# dev_A.net
KiCad netlist of a schematic drawn in EAGLE
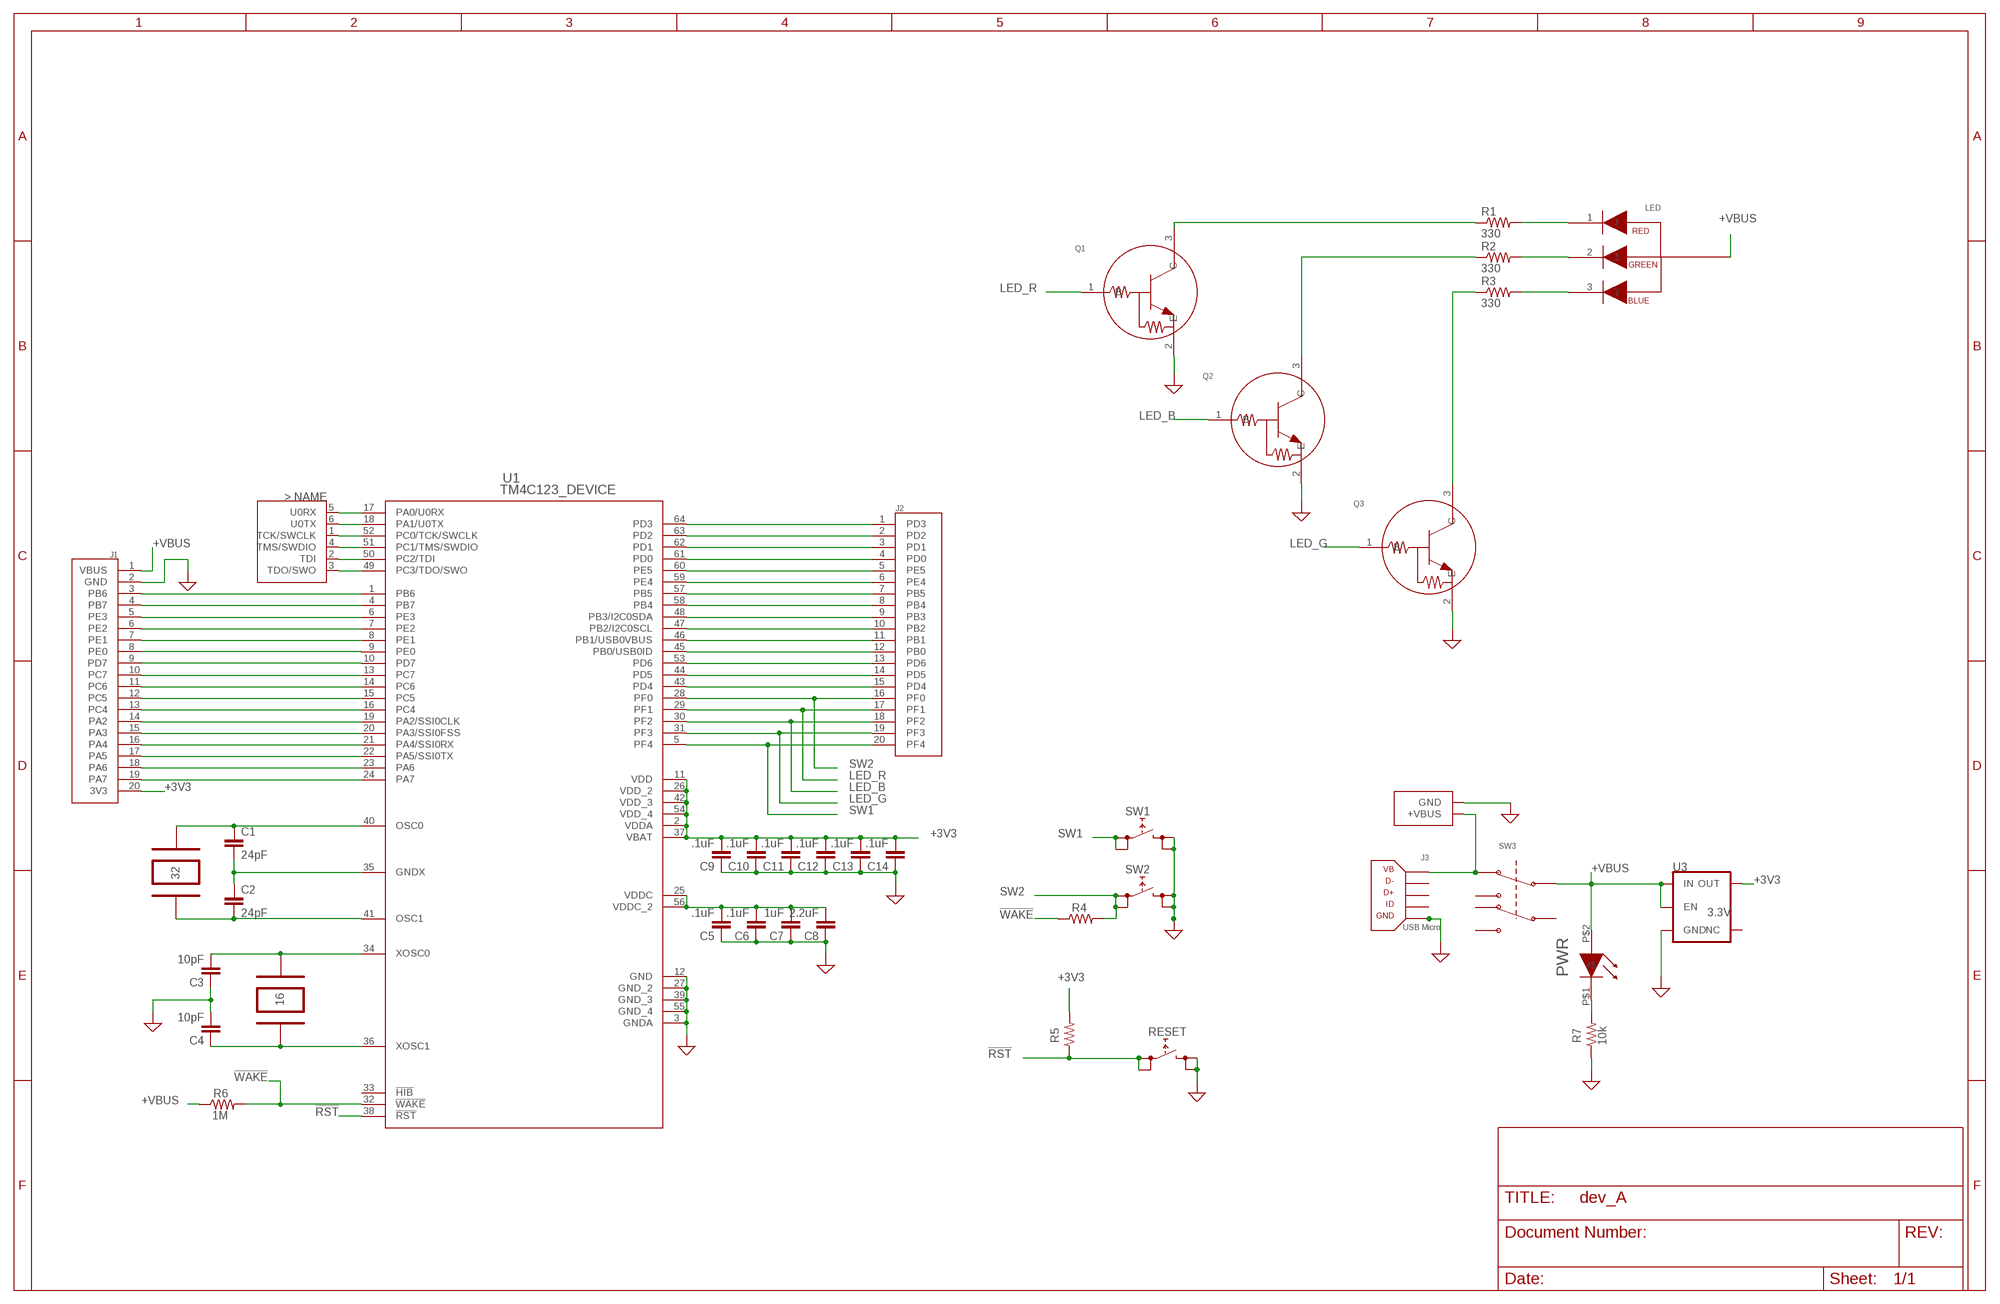
[diagram p0: schematic, sheet 1]

(export (version "E")
  (design (tool "Eeschema 10.0.6"))
  (components
    (comp (ref "C1")
      (value "24pF")
      (footprint "eagle-import:CAPC1005X35N")
      (libsource (lib "eagle-import") (part "CAPACITOR"))
    )
    (comp (ref "C2")
      (value "24pF")
      (footprint "eagle-import:CAPC1005X35N")
      (libsource (lib "eagle-import") (part "CAPACITOR"))
    )
    (comp (ref "C3")
      (value "10pF")
      (footprint "eagle-import:CAPC1005X35N")
      (libsource (lib "eagle-import") (part "CAPACITOR"))
    )
    (comp (ref "C4")
      (value "10pF")
      (footprint "eagle-import:CAPC1005X35N")
      (libsource (lib "eagle-import") (part "CAPACITOR"))
    )
    (comp (ref "C5")
      (value ".1uF")
      (footprint "eagle-import:CAPC1005X35N")
      (libsource (lib "eagle-import") (part "CAPACITOR"))
    )
    (comp (ref "C6")
      (value ".1uF")
      (footprint "eagle-import:CAPC1005X35N")
      (libsource (lib "eagle-import") (part "CAPACITOR"))
    )
    (comp (ref "C7")
      (value "1uF")
      (footprint "eagle-import:CAPC1005X35N")
      (libsource (lib "eagle-import") (part "CAPACITOR"))
    )
    (comp (ref "C8")
      (value "2.2uF")
      (footprint "eagle-import:CAPC1005X35N")
      (libsource (lib "eagle-import") (part "CAPACITOR"))
    )
    (comp (ref "C9")
      (value ".1uF")
      (footprint "eagle-import:CAPC1005X35N")
      (libsource (lib "eagle-import") (part "CAPACITOR"))
    )
    (comp (ref "C10")
      (value ".1uF")
      (footprint "eagle-import:CAPC1005X35N")
      (libsource (lib "eagle-import") (part "CAPACITOR"))
    )
    (comp (ref "C11")
      (value ".1uF")
      (footprint "eagle-import:CAPC1005X35N")
      (libsource (lib "eagle-import") (part "CAPACITOR"))
    )
    (comp (ref "C12")
      (value ".1uF")
      (footprint "eagle-import:CAPC1005X35N")
      (libsource (lib "eagle-import") (part "CAPACITOR"))
    )
    (comp (ref "C13")
      (value ".1uF")
      (footprint "eagle-import:CAPC1005X35N")
      (libsource (lib "eagle-import") (part "CAPACITOR"))
    )
    (comp (ref "C14")
      (value ".1uF")
      (footprint "eagle-import:CAPC1005X35N")
      (libsource (lib "eagle-import") (part "CAPACITOR"))
    )
    (comp (ref "DEBUG")
      (value "JTAG")
      (footprint "eagle-import:HDRV6W64P254_2X3_800X508X838B")
      (libsource (lib "eagle-import") (part "JTAG"))
    )
    (comp (ref "J1")
      (value "HEADER_J1")
      (footprint "eagle-import:HDRV20W80P254_1X20_5100X250X838B")
      (libsource (lib "eagle-import") (part "HEADER_J1"))
    )
    (comp (ref "J2")
      (value "HEADER_J2")
      (footprint "eagle-import:HDRV20W80P254_1X20_5100X250X838B")
      (libsource (lib "eagle-import") (part "HEADER_J2"))
    )
    (comp (ref "J3")
      (value "USBMICRO")
      (footprint "eagle-import:USBMICROB")
      (libsource (lib "eagle-import") (part "USBMICRO"))
    )
    (comp (ref "LED")
      (value "RGBLED")
      (footprint "eagle-import:RGBLED")
      (libsource (lib "eagle-import") (part "RGBLED"))
    )
    (comp (ref "PWR")
      (value "LED_511")
      (footprint "eagle-import:LED_511")
      (libsource (lib "eagle-import") (part "LED_511"))
    )
    (comp (ref "Q1")
      (value "NPN_BJT")
      (footprint "eagle-import:SOT416")
      (libsource (lib "eagle-import") (part "NPN_BJT"))
    )
    (comp (ref "Q2")
      (value "NPN_BJT")
      (footprint "eagle-import:SOT416")
      (libsource (lib "eagle-import") (part "NPN_BJT"))
    )
    (comp (ref "Q3")
      (value "NPN_BJT")
      (footprint "eagle-import:SOT416")
      (libsource (lib "eagle-import") (part "NPN_BJT"))
    )
    (comp (ref "R1")
      (value "330")
      (footprint "eagle-import:CAPC1005X35N")
      (libsource (lib "eagle-import") (part "RESISTOR"))
    )
    (comp (ref "R2")
      (value "330")
      (footprint "eagle-import:CAPC1005X35N")
      (libsource (lib "eagle-import") (part "RESISTOR"))
    )
    (comp (ref "R3")
      (value "330")
      (footprint "eagle-import:CAPC1005X35N")
      (libsource (lib "eagle-import") (part "RESISTOR"))
    )
    (comp (ref "R4")
      (value "RESISTOR")
      (footprint "eagle-import:CAPC1005X35N")
      (libsource (lib "eagle-import") (part "RESISTOR"))
    )
    (comp (ref "R5")
      (value "RESISTOR")
      (footprint "eagle-import:CAPC1005X35N")
      (libsource (lib "eagle-import") (part "RESISTOR"))
    )
    (comp (ref "R6")
      (value "1M")
      (footprint "eagle-import:CAPC1005X35N")
      (libsource (lib "eagle-import") (part "RESISTOR"))
    )
    (comp (ref "R7")
      (value "10k")
      (footprint "eagle-import:CAPC1005X35N")
      (libsource (lib "eagle-import") (part "RESISTOR"))
    )
    (comp (ref "RESET")
      (value "SWITCH_B3S")
      (footprint "eagle-import:SW_BS3")
      (libsource (lib "eagle-import") (part "SWITCH_B3S"))
    )
    (comp (ref "SW1")
      (value "SWITCH_B3S")
      (footprint "eagle-import:SW_BS3")
      (libsource (lib "eagle-import") (part "SWITCH_B3S"))
    )
    (comp (ref "SW2")
      (value "SWITCH_B3S")
      (footprint "eagle-import:SW_BS3")
      (libsource (lib "eagle-import") (part "SWITCH_B3S"))
    )
    (comp (ref "SW3")
      (value "JS202011SCQN")
      (footprint "eagle-import:SW_JS202011SCQN")
      (libsource (lib "eagle-import") (part "JS202011SCQN"))
    )
    (comp (ref "U1")
      (value "TM4C123_DEVICE")
      (footprint "eagle-import:TM3C123_FOOTPRINT")
      (libsource (lib "eagle-import") (part "TM4C123_DEVICE"))
    )
    (comp (ref "U3")
      (value "3.3V")
      (footprint "eagle-import:SOT23-5")
      (libsource (lib "eagle-import") (part "V_REG_AP2112K-3.3V"))
    )
    (comp (ref "VBUS")
      (value "POWER")
      (footprint "eagle-import:HDRV2W64P254_1X2_600X300X838B")
      (libsource (lib "eagle-import") (part "POWER"))
    )
    (comp (ref "Y1")
      (value "32kHz")
      (footprint "eagle-import:GHI2_CRYSTAL_3.2X1.5")
      (libsource (lib "eagle-import") (part "32KHZ_OSCILATOR"))
    )
    (comp (ref "Y2")
      (value "Y2")
      (footprint "eagle-import:CRYSTAL_16MHZ")
      (libsource (lib "eagle-import") (part "16MHZ_OSCILLATOR"))
    )
  )
  (nets
    (net (code "1") (name "/+3V3") (class "Default")
      (node (ref "C10") (pin "2") (pinfunction "2_2") (pintype "passive"))
      (node (ref "C11") (pin "2") (pinfunction "2_2") (pintype "passive"))
      (node (ref "C12") (pin "2") (pinfunction "2_2") (pintype "passive"))
      (node (ref "C13") (pin "2") (pinfunction "2_2") (pintype "passive"))
      (node (ref "C14") (pin "2") (pinfunction "2_2") (pintype "passive"))
      (node (ref "C9") (pin "2") (pinfunction "2_2") (pintype "passive"))
      (node (ref "J1") (pin "20") (pinfunction "3V3_20") (pintype "bidirectional"))
      (node (ref "R5") (pin "2") (pinfunction "2_2") (pintype "passive"))
      (node (ref "U1") (pin "11") (pinfunction "VDD_11") (pintype "power_in"))
      (node (ref "U1") (pin "2") (pinfunction "VDDA_2") (pintype "power_in"))
      (node (ref "U1") (pin "26") (pinfunction "VDD_2_26") (pintype "power_in"))
      (node (ref "U1") (pin "37") (pinfunction "VBAT_37") (pintype "power_in"))
      (node (ref "U1") (pin "42") (pinfunction "VDD_3_42") (pintype "power_in"))
      (node (ref "U1") (pin "54") (pinfunction "VDD_4_54") (pintype "power_in"))
      (node (ref "U3") (pin "5") (pinfunction "OUT_5") (pintype "passive"))
    )
    (net (code "2") (name "/+VBUS") (class "Default")
      (node (ref "J1") (pin "1") (pinfunction "VBUS_1") (pintype "bidirectional"))
      (node (ref "LED") (pin "4") (pinfunction "4_4") (pintype "passive"))
      (node (ref "PWR") (pin "P$2") (pinfunction "2_P$2") (pintype "bidirectional"))
      (node (ref "R6") (pin "1") (pinfunction "1_1") (pintype "passive"))
      (node (ref "SW3") (pin "2") (pinfunction "2_2") (pintype "passive"))
      (node (ref "U3") (pin "1") (pinfunction "IN_1") (pintype "input"))
      (node (ref "U3") (pin "3") (pinfunction "EN_3") (pintype "input"))
    )
    (net (code "3") (name "/LED_B") (class "Default")
      (node (ref "J2") (pin "18") (pinfunction "PF2_18") (pintype "bidirectional"))
      (node (ref "Q2") (pin "1") (pinfunction "B_1") (pintype "bidirectional"))
      (node (ref "U1") (pin "30") (pinfunction "PF2_30") (pintype "bidirectional"))
    )
    (net (code "4") (name "/LED_G") (class "Default")
      (node (ref "J2") (pin "19") (pinfunction "PF3_19") (pintype "bidirectional"))
      (node (ref "Q3") (pin "1") (pinfunction "B_1") (pintype "bidirectional"))
      (node (ref "U1") (pin "31") (pinfunction "PF3_31") (pintype "bidirectional"))
    )
    (net (code "5") (name "/LED_R") (class "Default")
      (node (ref "J2") (pin "17") (pinfunction "PF1_17") (pintype "bidirectional"))
      (node (ref "Q1") (pin "1") (pinfunction "B_1") (pintype "bidirectional"))
      (node (ref "U1") (pin "29") (pinfunction "PF1_29") (pintype "bidirectional"))
    )
    (net (code "6") (name "/SW1") (class "Default")
      (node (ref "J2") (pin "20") (pinfunction "PF4_20") (pintype "bidirectional"))
      (node (ref "SW1") (pin "1") (pinfunction "1_1") (pintype "passive"))
      (node (ref "SW1") (pin "2") (pinfunction "2_2") (pintype "passive"))
      (node (ref "U1") (pin "5") (pinfunction "PF4_5") (pintype "bidirectional"))
    )
    (net (code "7") (name "/SW2") (class "Default")
      (node (ref "J2") (pin "16") (pinfunction "PF0_16") (pintype "bidirectional"))
      (node (ref "R4") (pin "2") (pinfunction "2_2") (pintype "passive"))
      (node (ref "SW2") (pin "1") (pinfunction "1_1") (pintype "passive"))
      (node (ref "SW2") (pin "2") (pinfunction "2_2") (pintype "passive"))
      (node (ref "U1") (pin "28") (pinfunction "PF0_28") (pintype "bidirectional"))
    )
    (net (code "8") (name "/~{RST}") (class "Default")
      (node (ref "R5") (pin "1") (pinfunction "1_1") (pintype "passive"))
      (node (ref "RESET") (pin "1") (pinfunction "1_1") (pintype "passive"))
      (node (ref "RESET") (pin "2") (pinfunction "2_2") (pintype "passive"))
      (node (ref "U1") (pin "38") (pinfunction "~{RST}_38") (pintype "input"))
    )
    (net (code "9") (name "/~{WAKE}") (class "Default")
      (node (ref "R4") (pin "1") (pinfunction "1_1") (pintype "passive"))
      (node (ref "R6") (pin "2") (pinfunction "2_2") (pintype "passive"))
      (node (ref "U1") (pin "32") (pinfunction "~{WAKE}_32") (pintype "input"))
    )
    (net (code "10") (name "Net-(DEBUG-TCK{slash}SWCLK)") (class "Default")
      (node (ref "DEBUG") (pin "1") (pinfunction "TCK/SWCLK_1") (pintype "bidirectional"))
      (node (ref "U1") (pin "52") (pinfunction "PC0/TCK/SWCLK_52") (pintype "bidirectional"))
    )
    (net (code "11") (name "Net-(DEBUG-TDI)") (class "Default")
      (node (ref "DEBUG") (pin "2") (pinfunction "TDI_2") (pintype "bidirectional"))
      (node (ref "U1") (pin "50") (pinfunction "PC2/TDI_50") (pintype "bidirectional"))
    )
    (net (code "12") (name "Net-(DEBUG-TDO{slash}SWO)") (class "Default")
      (node (ref "DEBUG") (pin "3") (pinfunction "TDO/SWO_3") (pintype "bidirectional"))
      (node (ref "U1") (pin "49") (pinfunction "PC3/TDO/SWO_49") (pintype "bidirectional"))
    )
    (net (code "13") (name "Net-(DEBUG-TMS{slash}SWDIO)") (class "Default")
      (node (ref "DEBUG") (pin "4") (pinfunction "TMS/SWDIO_4") (pintype "bidirectional"))
      (node (ref "U1") (pin "51") (pinfunction "PC1/TMS/SWDIO_51") (pintype "bidirectional"))
    )
    (net (code "14") (name "Net-(DEBUG-U0RX)") (class "Default")
      (node (ref "DEBUG") (pin "5") (pinfunction "U0RX_5") (pintype "bidirectional"))
      (node (ref "U1") (pin "17") (pinfunction "PA0/U0RX_17") (pintype "bidirectional"))
    )
    (net (code "15") (name "Net-(DEBUG-U0TX)") (class "Default")
      (node (ref "DEBUG") (pin "6") (pinfunction "U0TX_6") (pintype "bidirectional"))
      (node (ref "U1") (pin "18") (pinfunction "PA1/U0TX_18") (pintype "bidirectional"))
    )
    (net (code "16") (name "Net-(J1-PA2)") (class "Default")
      (node (ref "J1") (pin "14") (pinfunction "PA2_14") (pintype "bidirectional"))
      (node (ref "U1") (pin "19") (pinfunction "PA2/SSI0CLK_19") (pintype "bidirectional"))
    )
    (net (code "17") (name "Net-(J1-PA3)") (class "Default")
      (node (ref "J1") (pin "15") (pinfunction "PA3_15") (pintype "bidirectional"))
      (node (ref "U1") (pin "20") (pinfunction "PA3/SSI0FSS_20") (pintype "bidirectional"))
    )
    (net (code "18") (name "Net-(J1-PA4)") (class "Default")
      (node (ref "J1") (pin "16") (pinfunction "PA4_16") (pintype "bidirectional"))
      (node (ref "U1") (pin "21") (pinfunction "PA4/SSI0RX_21") (pintype "bidirectional"))
    )
    (net (code "19") (name "Net-(J1-PA5)") (class "Default")
      (node (ref "J1") (pin "17") (pinfunction "PA5_17") (pintype "bidirectional"))
      (node (ref "U1") (pin "22") (pinfunction "PA5/SSI0TX_22") (pintype "bidirectional"))
    )
    (net (code "20") (name "Net-(J1-PA6)") (class "Default")
      (node (ref "J1") (pin "18") (pinfunction "PA6_18") (pintype "bidirectional"))
      (node (ref "U1") (pin "23") (pinfunction "PA6_23") (pintype "bidirectional"))
    )
    (net (code "21") (name "Net-(J1-PA7)") (class "Default")
      (node (ref "J1") (pin "19") (pinfunction "PA7_19") (pintype "bidirectional"))
      (node (ref "U1") (pin "24") (pinfunction "PA7_24") (pintype "bidirectional"))
    )
    (net (code "22") (name "Net-(J1-PB6)") (class "Default")
      (node (ref "J1") (pin "3") (pinfunction "PB6_3") (pintype "bidirectional"))
      (node (ref "U1") (pin "1") (pinfunction "PB6_1") (pintype "bidirectional"))
    )
    (net (code "23") (name "Net-(J1-PB7)") (class "Default")
      (node (ref "J1") (pin "4") (pinfunction "PB7_4") (pintype "bidirectional"))
      (node (ref "U1") (pin "4") (pinfunction "PB7_4") (pintype "bidirectional"))
    )
    (net (code "24") (name "Net-(J1-PC4)") (class "Default")
      (node (ref "J1") (pin "13") (pinfunction "PC4_13") (pintype "bidirectional"))
      (node (ref "U1") (pin "16") (pinfunction "PC4_16") (pintype "bidirectional"))
    )
    (net (code "25") (name "Net-(J1-PC5)") (class "Default")
      (node (ref "J1") (pin "12") (pinfunction "PC5_12") (pintype "bidirectional"))
      (node (ref "U1") (pin "15") (pinfunction "PC5_15") (pintype "bidirectional"))
    )
    (net (code "26") (name "Net-(J1-PC6)") (class "Default")
      (node (ref "J1") (pin "11") (pinfunction "PC6_11") (pintype "bidirectional"))
      (node (ref "U1") (pin "14") (pinfunction "PC6_14") (pintype "bidirectional"))
    )
    (net (code "27") (name "Net-(J1-PC7)") (class "Default")
      (node (ref "J1") (pin "10") (pinfunction "PC7_10") (pintype "bidirectional"))
      (node (ref "U1") (pin "13") (pinfunction "PC7_13") (pintype "bidirectional"))
    )
    (net (code "28") (name "Net-(J1-PD7)") (class "Default")
      (node (ref "J1") (pin "9") (pinfunction "PD7_9") (pintype "bidirectional"))
      (node (ref "U1") (pin "10") (pinfunction "PD7_10") (pintype "bidirectional"))
    )
    (net (code "29") (name "Net-(J1-PE0)") (class "Default")
      (node (ref "J1") (pin "8") (pinfunction "PE0_8") (pintype "bidirectional"))
      (node (ref "U1") (pin "9") (pinfunction "PE0_9") (pintype "bidirectional"))
    )
    (net (code "30") (name "Net-(J1-PE1)") (class "Default")
      (node (ref "J1") (pin "7") (pinfunction "PE1_7") (pintype "bidirectional"))
      (node (ref "U1") (pin "8") (pinfunction "PE1_8") (pintype "bidirectional"))
    )
    (net (code "31") (name "Net-(J1-PE2)") (class "Default")
      (node (ref "J1") (pin "6") (pinfunction "PE2_6") (pintype "bidirectional"))
      (node (ref "U1") (pin "7") (pinfunction "PE2_7") (pintype "bidirectional"))
    )
    (net (code "32") (name "Net-(J1-PE3)") (class "Default")
      (node (ref "J1") (pin "5") (pinfunction "PE3_5") (pintype "bidirectional"))
      (node (ref "U1") (pin "6") (pinfunction "PE3_6") (pintype "bidirectional"))
    )
    (net (code "33") (name "Net-(J2-PB0)") (class "Default")
      (node (ref "J2") (pin "12") (pinfunction "PB0_12") (pintype "bidirectional"))
      (node (ref "U1") (pin "45") (pinfunction "PB0/USB0ID_45") (pintype "bidirectional"))
    )
    (net (code "34") (name "Net-(J2-PB1)") (class "Default")
      (node (ref "J2") (pin "11") (pinfunction "PB1_11") (pintype "bidirectional"))
      (node (ref "U1") (pin "46") (pinfunction "PB1/USB0VBUS_46") (pintype "bidirectional"))
    )
    (net (code "35") (name "Net-(J2-PB2)") (class "Default")
      (node (ref "J2") (pin "10") (pinfunction "PB2_10") (pintype "bidirectional"))
      (node (ref "U1") (pin "47") (pinfunction "PB2/I2C0SCL_47") (pintype "bidirectional"))
    )
    (net (code "36") (name "Net-(J2-PB3)") (class "Default")
      (node (ref "J2") (pin "9") (pinfunction "PB3_9") (pintype "bidirectional"))
      (node (ref "U1") (pin "48") (pinfunction "PB3/I2C0SDA_48") (pintype "bidirectional"))
    )
    (net (code "37") (name "Net-(J2-PB4)") (class "Default")
      (node (ref "J2") (pin "8") (pinfunction "PB4_8") (pintype "bidirectional"))
      (node (ref "U1") (pin "58") (pinfunction "PB4_58") (pintype "bidirectional"))
    )
    (net (code "38") (name "Net-(J2-PB5)") (class "Default")
      (node (ref "J2") (pin "7") (pinfunction "PB5_7") (pintype "bidirectional"))
      (node (ref "U1") (pin "57") (pinfunction "PB5_57") (pintype "bidirectional"))
    )
    (net (code "39") (name "Net-(J2-PD0)") (class "Default")
      (node (ref "J2") (pin "4") (pinfunction "PD0_4") (pintype "bidirectional"))
      (node (ref "U1") (pin "61") (pinfunction "PD0_61") (pintype "bidirectional"))
    )
    (net (code "40") (name "Net-(J2-PD1)") (class "Default")
      (node (ref "J2") (pin "3") (pinfunction "PD1_3") (pintype "bidirectional"))
      (node (ref "U1") (pin "62") (pinfunction "PD1_62") (pintype "bidirectional"))
    )
    (net (code "41") (name "Net-(J2-PD2)") (class "Default")
      (node (ref "J2") (pin "2") (pinfunction "PD2_2") (pintype "bidirectional"))
      (node (ref "U1") (pin "63") (pinfunction "PD2_63") (pintype "bidirectional"))
    )
    (net (code "42") (name "Net-(J2-PD3)") (class "Default")
      (node (ref "J2") (pin "1") (pinfunction "PD3_1") (pintype "bidirectional"))
      (node (ref "U1") (pin "64") (pinfunction "PD3_64") (pintype "bidirectional"))
    )
    (net (code "43") (name "Net-(J2-PD4)") (class "Default")
      (node (ref "J2") (pin "15") (pinfunction "PD4_15") (pintype "bidirectional"))
      (node (ref "U1") (pin "43") (pinfunction "PD4_43") (pintype "bidirectional"))
    )
    (net (code "44") (name "Net-(J2-PD5)") (class "Default")
      (node (ref "J2") (pin "14") (pinfunction "PD5_14") (pintype "bidirectional"))
      (node (ref "U1") (pin "44") (pinfunction "PD5_44") (pintype "bidirectional"))
    )
    (net (code "45") (name "Net-(J2-PD6)") (class "Default")
      (node (ref "J2") (pin "13") (pinfunction "PD6_13") (pintype "bidirectional"))
      (node (ref "U1") (pin "53") (pinfunction "PD6_53") (pintype "bidirectional"))
    )
    (net (code "46") (name "Net-(J2-PE4)") (class "Default")
      (node (ref "J2") (pin "6") (pinfunction "PE4_6") (pintype "bidirectional"))
      (node (ref "U1") (pin "59") (pinfunction "PE4_59") (pintype "bidirectional"))
    )
    (net (code "47") (name "Net-(J2-PE5)") (class "Default")
      (node (ref "J2") (pin "5") (pinfunction "PE5_5") (pintype "bidirectional"))
      (node (ref "U1") (pin "60") (pinfunction "PE5_60") (pintype "bidirectional"))
    )
    (net (code "48") (name "Net-(J3-1)") (class "Default")
      (node (ref "J3") (pin "VB") (pinfunction "1_VB") (pintype "passive"))
      (node (ref "SW3") (pin "1") (pinfunction "1_1") (pintype "passive"))
      (node (ref "VBUS") (pin "1") (pinfunction "+VBUS_1") (pintype "bidirectional"))
    )
    (net (code "49") (name "Net-(LED-Pad1)") (class "Default")
      (node (ref "LED") (pin "1") (pinfunction "1_1") (pintype "passive"))
      (node (ref "R1") (pin "2") (pinfunction "2_2") (pintype "passive"))
    )
    (net (code "50") (name "Net-(LED-Pad2)") (class "Default")
      (node (ref "LED") (pin "2") (pinfunction "2_2") (pintype "passive"))
      (node (ref "R2") (pin "2") (pinfunction "2_2") (pintype "passive"))
    )
    (net (code "51") (name "Net-(LED-Pad3)") (class "Default")
      (node (ref "LED") (pin "3") (pinfunction "3_3") (pintype "passive"))
      (node (ref "R3") (pin "2") (pinfunction "2_2") (pintype "passive"))
    )
    (net (code "52") (name "Net-(PWR-1)") (class "Default")
      (node (ref "PWR") (pin "P$1") (pinfunction "1_P$1") (pintype "bidirectional"))
      (node (ref "R7") (pin "2") (pinfunction "2_2") (pintype "passive"))
    )
    (net (code "53") (name "Net-(Q1-C)") (class "Default")
      (node (ref "Q1") (pin "3") (pinfunction "C_3") (pintype "bidirectional"))
      (node (ref "R1") (pin "1") (pinfunction "1_1") (pintype "passive"))
    )
    (net (code "54") (name "Net-(Q2-C)") (class "Default")
      (node (ref "Q2") (pin "3") (pinfunction "C_3") (pintype "bidirectional"))
      (node (ref "R2") (pin "1") (pinfunction "1_1") (pintype "passive"))
    )
    (net (code "55") (name "Net-(Q3-C)") (class "Default")
      (node (ref "Q3") (pin "3") (pinfunction "C_3") (pintype "bidirectional"))
      (node (ref "R3") (pin "1") (pinfunction "1_1") (pintype "passive"))
    )
    (net (code "56") (name "Net-(U1-GNDX)") (class "Default")
      (node (ref "C1") (pin "2") (pinfunction "2_2") (pintype "passive"))
      (node (ref "C2") (pin "1") (pinfunction "1_1") (pintype "passive"))
      (node (ref "U1") (pin "35") (pinfunction "GNDX_35") (pintype "power_in"))
    )
    (net (code "57") (name "Net-(U1-OSC0)") (class "Default")
      (node (ref "C1") (pin "1") (pinfunction "1_1") (pintype "passive"))
      (node (ref "U1") (pin "40") (pinfunction "OSC0_40") (pintype "input"))
      (node (ref "Y1") (pin "P$2") (pinfunction "2_P$2") (pintype "passive"))
    )
    (net (code "58") (name "Net-(U1-OSC1)") (class "Default")
      (node (ref "C2") (pin "2") (pinfunction "2_2") (pintype "passive"))
      (node (ref "U1") (pin "41") (pinfunction "OSC1_41") (pintype "output"))
      (node (ref "Y1") (pin "P$1") (pinfunction "1_P$1") (pintype "passive"))
    )
    (net (code "59") (name "Net-(U1-VDDC)") (class "Default")
      (node (ref "C5") (pin "2") (pinfunction "2_2") (pintype "passive"))
      (node (ref "C6") (pin "2") (pinfunction "2_2") (pintype "passive"))
      (node (ref "C7") (pin "2") (pinfunction "2_2") (pintype "passive"))
      (node (ref "C8") (pin "2") (pinfunction "2_2") (pintype "passive"))
      (node (ref "U1") (pin "25") (pinfunction "VDDC_25") (pintype "power_in"))
      (node (ref "U1") (pin "56") (pinfunction "VDDC_2_56") (pintype "power_in"))
    )
    (net (code "60") (name "Net-(U1-XOSC0)") (class "Default")
      (node (ref "C3") (pin "2") (pinfunction "2_2") (pintype "passive"))
      (node (ref "U1") (pin "34") (pinfunction "XOSC0_34") (pintype "input"))
      (node (ref "Y2") (pin "2") (pinfunction "2_2") (pintype "passive"))
    )
    (net (code "61") (name "Net-(U1-XOSC1)") (class "Default")
      (node (ref "C4") (pin "1") (pinfunction "1_1") (pintype "passive"))
      (node (ref "U1") (pin "36") (pinfunction "XOSC1_36") (pintype "output"))
      (node (ref "Y2") (pin "1") (pinfunction "1_1") (pintype "passive"))
    )
    (net (code "62") (name "SUP") (class "Default")
      (node (ref "C10") (pin "1") (pinfunction "1_1") (pintype "passive"))
      (node (ref "C11") (pin "1") (pinfunction "1_1") (pintype "passive"))
      (node (ref "C12") (pin "1") (pinfunction "1_1") (pintype "passive"))
      (node (ref "C13") (pin "1") (pinfunction "1_1") (pintype "passive"))
      (node (ref "C14") (pin "1") (pinfunction "1_1") (pintype "passive"))
      (node (ref "C3") (pin "1") (pinfunction "1_1") (pintype "passive"))
      (node (ref "C4") (pin "2") (pinfunction "2_2") (pintype "passive"))
      (node (ref "C5") (pin "1") (pinfunction "1_1") (pintype "passive"))
      (node (ref "C6") (pin "1") (pinfunction "1_1") (pintype "passive"))
      (node (ref "C7") (pin "1") (pinfunction "1_1") (pintype "passive"))
      (node (ref "C8") (pin "1") (pinfunction "1_1") (pintype "passive"))
      (node (ref "C9") (pin "1") (pinfunction "1_1") (pintype "passive"))
      (node (ref "J1") (pin "2") (pinfunction "GND_2") (pintype "bidirectional"))
      (node (ref "J3") (pin "0") (pinfunction "GND_0") (pintype "passive"))
      (node (ref "J3") (pin "01") (pinfunction "GND_01") (pintype "passive"))
      (node (ref "J3") (pin "02") (pinfunction "GND_02") (pintype "passive"))
      (node (ref "J3") (pin "03") (pinfunction "GND_03") (pintype "passive"))
      (node (ref "J3") (pin "GND") (pinfunction "GND_GND") (pintype "passive"))
      (node (ref "Q1") (pin "2") (pinfunction "E_2") (pintype "bidirectional"))
      (node (ref "Q2") (pin "2") (pinfunction "E_2") (pintype "bidirectional"))
      (node (ref "Q3") (pin "2") (pinfunction "E_2") (pintype "bidirectional"))
      (node (ref "R7") (pin "1") (pinfunction "1_1") (pintype "passive"))
      (node (ref "RESET") (pin "3") (pinfunction "3_3") (pintype "passive"))
      (node (ref "RESET") (pin "4") (pinfunction "4_4") (pintype "passive"))
      (node (ref "SW1") (pin "3") (pinfunction "3_3") (pintype "passive"))
      (node (ref "SW1") (pin "4") (pinfunction "4_4") (pintype "passive"))
      (node (ref "SW2") (pin "3") (pinfunction "3_3") (pintype "passive"))
      (node (ref "SW2") (pin "4") (pinfunction "4_4") (pintype "passive"))
      (node (ref "U1") (pin "12") (pinfunction "GND_12") (pintype "power_in"))
      (node (ref "U1") (pin "27") (pinfunction "GND_2_27") (pintype "power_in"))
      (node (ref "U1") (pin "3") (pinfunction "GNDA_3") (pintype "power_in"))
      (node (ref "U1") (pin "39") (pinfunction "GND_3_39") (pintype "power_in"))
      (node (ref "U1") (pin "55") (pinfunction "GND_4_55") (pintype "power_in"))
      (node (ref "U3") (pin "2") (pinfunction "GND_2") (pintype "input"))
      (node (ref "VBUS") (pin "2") (pinfunction "GND_2") (pintype "bidirectional"))
    )
    (net (code "63") (name "unconnected-(J3-2-PadD-)") (class "Default")
      (node (ref "J3") (pin "D-") (pinfunction "2_D-") (pintype "passive"))
    )
    (net (code "64") (name "unconnected-(J3-3-PadD+)") (class "Default")
      (node (ref "J3") (pin "D+") (pinfunction "3_D+") (pintype "passive"))
    )
    (net (code "65") (name "unconnected-(J3-4-PadID)") (class "Default")
      (node (ref "J3") (pin "ID") (pinfunction "4_ID") (pintype "passive"))
    )
    (net (code "66") (name "unconnected-(SW3-Pad3)") (class "Default")
      (node (ref "SW3") (pin "3") (pinfunction "3_3") (pintype "passive"))
    )
    (net (code "67") (name "unconnected-(SW3-Pad4)") (class "Default")
      (node (ref "SW3") (pin "4") (pinfunction "4_4") (pintype "passive"))
    )
    (net (code "68") (name "unconnected-(SW3-Pad5)") (class "Default")
      (node (ref "SW3") (pin "5") (pinfunction "5_5") (pintype "passive"))
    )
    (net (code "69") (name "unconnected-(SW3-Pad6)") (class "Default")
      (node (ref "SW3") (pin "6") (pinfunction "6_6") (pintype "passive"))
    )
    (net (code "70") (name "unconnected-(U1-~{HIB}-Pad33)") (class "Default")
      (node (ref "U1") (pin "33") (pinfunction "~{HIB}_33") (pintype "output"))
    )
    (net (code "71") (name "unconnected-(U3-NC-Pad4)") (class "Default")
      (node (ref "U3") (pin "4") (pinfunction "NC_4") (pintype "no_connect"))
    )
  )
)
